# Sheet2.net
KiCad netlist of a schematic drawn in Altium Designer
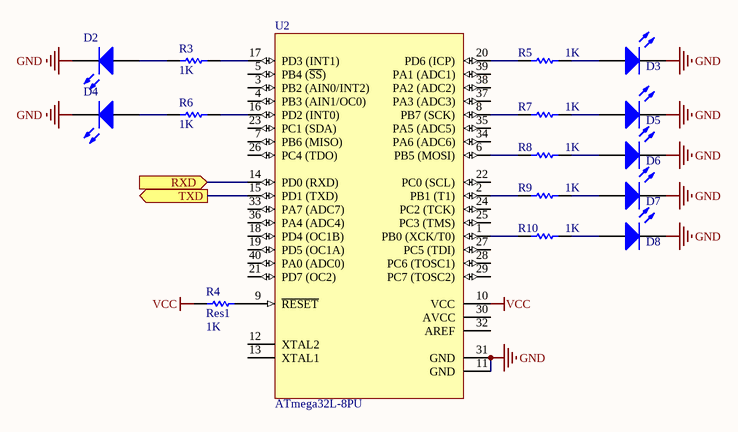
[diagram p0: Sheet2.SchDoc]

(export (version "E")
  (design (tool "Eeschema 10.0.6"))
  (components
    (comp (ref "D2")
      (value "LED0")
      (footprint "LED-0")
      (description "Typical INFRARED GaAs LED")
      (fields (field (name "PUBLISHER") "Altium Limited"))
      (libsource (lib "Miscellaneous Devices") (part "LED0"))
    )
    (comp (ref "D3")
      (value "LED0")
      (footprint "LED-0")
      (description "Typical INFRARED GaAs LED")
      (fields (field (name "PUBLISHER") "Altium Limited"))
      (libsource (lib "Miscellaneous Devices") (part "LED0"))
    )
    (comp (ref "D4")
      (value "LED0")
      (footprint "LED-0")
      (description "Typical INFRARED GaAs LED")
      (fields (field (name "PUBLISHER") "Altium Limited"))
      (libsource (lib "Miscellaneous Devices") (part "LED0"))
    )
    (comp (ref "D5")
      (value "LED0")
      (footprint "LED-0")
      (description "Typical INFRARED GaAs LED")
      (fields (field (name "PUBLISHER") "Altium Limited"))
      (libsource (lib "Miscellaneous Devices") (part "LED0"))
    )
    (comp (ref "D6")
      (value "LED0")
      (footprint "LED-0")
      (description "Typical INFRARED GaAs LED")
      (fields (field (name "PUBLISHER") "Altium Limited"))
      (libsource (lib "Miscellaneous Devices") (part "LED0"))
    )
    (comp (ref "D7")
      (value "LED0")
      (footprint "LED-0")
      (description "Typical INFRARED GaAs LED")
      (fields (field (name "PUBLISHER") "Altium Limited"))
      (libsource (lib "Miscellaneous Devices") (part "LED0"))
    )
    (comp (ref "D8")
      (value "LED0")
      (footprint "LED-0")
      (description "Typical INFRARED GaAs LED")
      (fields (field (name "PUBLISHER") "Altium Limited"))
      (libsource (lib "Miscellaneous Devices") (part "LED0"))
    )
    (comp (ref "R3")
      (value "1K")
      (footprint "AXIAL-0.3")
      (description "Resistor")
      (fields (field (name "Comment") "Res1") (field (name "PUBLISHER") "Altium Limited"))
      (libsource (lib "Miscellaneous Devices") (part "Res1"))
    )
    (comp (ref "R4")
      (value "Res1")
      (footprint "AXIAL-0.3")
      (description "Resistor")
      (fields (field (name "ALTIUM_VALUE") "1K") (field (name "PUBLISHER") "Altium Limited"))
      (libsource (lib "Miscellaneous Devices") (part "Res1"))
    )
    (comp (ref "R5")
      (value "1K")
      (footprint "AXIAL-0.3")
      (description "Resistor")
      (fields (field (name "Comment") "Res1") (field (name "PUBLISHER") "Altium Limited"))
      (libsource (lib "Miscellaneous Devices") (part "Res1"))
    )
    (comp (ref "R6")
      (value "1K")
      (footprint "AXIAL-0.3")
      (description "Resistor")
      (fields (field (name "Comment") "Res1") (field (name "PUBLISHER") "Altium Limited"))
      (libsource (lib "Miscellaneous Devices") (part "Res1"))
    )
    (comp (ref "R7")
      (value "1K")
      (footprint "AXIAL-0.3")
      (description "Resistor")
      (fields (field (name "Comment") "Res1") (field (name "PUBLISHER") "Altium Limited"))
      (libsource (lib "Miscellaneous Devices") (part "Res1"))
    )
    (comp (ref "R8")
      (value "1K")
      (footprint "AXIAL-0.3")
      (description "Resistor")
      (fields (field (name "Comment") "Res1") (field (name "PUBLISHER") "Altium Limited"))
      (libsource (lib "Miscellaneous Devices") (part "Res1"))
    )
    (comp (ref "R9")
      (value "1K")
      (footprint "AXIAL-0.3")
      (description "Resistor")
      (fields (field (name "Comment") "Res1") (field (name "PUBLISHER") "Altium Limited"))
      (libsource (lib "Miscellaneous Devices") (part "Res1"))
    )
    (comp (ref "R10")
      (value "1K")
      (footprint "AXIAL-0.3")
      (description "Resistor")
      (fields (field (name "Comment") "Res1") (field (name "PUBLISHER") "Altium Limited"))
      (libsource (lib "Miscellaneous Devices") (part "Res1"))
    )
    (comp (ref "U2")
      (value "ATmega32L-8PU")
      (footprint "40P6")
      (libsource (lib "Atmel Microcontroller megaAVR") (part "ATmega32L-8PU"))
    )
  )
  (nets
    (net (code "1") (name "/RXD") (class "Default")
      (node (ref "U2") (pin "14") (pinfunction "PD0_(RXD)_14") (pintype "bidirectional"))
    )
    (net (code "2") (name "/TXD") (class "Default")
      (node (ref "U2") (pin "15") (pinfunction "PD1_(TXD)_15") (pintype "bidirectional"))
    )
    (net (code "3") (name "GND") (class "Default")
      (node (ref "D2") (pin "2") (pinfunction "K_2") (pintype "passive"))
      (node (ref "D3") (pin "2") (pinfunction "K_2") (pintype "passive"))
      (node (ref "D4") (pin "2") (pinfunction "K_2") (pintype "passive"))
      (node (ref "D5") (pin "2") (pinfunction "K_2") (pintype "passive"))
      (node (ref "D6") (pin "2") (pinfunction "K_2") (pintype "passive"))
      (node (ref "D7") (pin "2") (pinfunction "K_2") (pintype "passive"))
      (node (ref "D8") (pin "2") (pinfunction "K_2") (pintype "passive"))
      (node (ref "U2") (pin "11") (pinfunction "GND_11") (pintype "power_in"))
      (node (ref "U2") (pin "31") (pinfunction "GND_31") (pintype "power_in"))
    )
    (net (code "4") (name "Net-(D2-A)") (class "Default")
      (node (ref "D2") (pin "1") (pinfunction "A_1") (pintype "passive"))
      (node (ref "R3") (pin "2") (pinfunction "2_2") (pintype "passive"))
    )
    (net (code "5") (name "Net-(D3-A)") (class "Default")
      (node (ref "D3") (pin "1") (pinfunction "A_1") (pintype "passive"))
      (node (ref "R5") (pin "2") (pinfunction "2_2") (pintype "passive"))
    )
    (net (code "6") (name "Net-(D4-A)") (class "Default")
      (node (ref "D4") (pin "1") (pinfunction "A_1") (pintype "passive"))
      (node (ref "R6") (pin "2") (pinfunction "2_2") (pintype "passive"))
    )
    (net (code "7") (name "Net-(D5-A)") (class "Default")
      (node (ref "D5") (pin "1") (pinfunction "A_1") (pintype "passive"))
      (node (ref "R7") (pin "2") (pinfunction "2_2") (pintype "passive"))
    )
    (net (code "8") (name "Net-(D6-A)") (class "Default")
      (node (ref "D6") (pin "1") (pinfunction "A_1") (pintype "passive"))
      (node (ref "R8") (pin "2") (pinfunction "2_2") (pintype "passive"))
    )
    (net (code "9") (name "Net-(D7-A)") (class "Default")
      (node (ref "D7") (pin "1") (pinfunction "A_1") (pintype "passive"))
      (node (ref "R9") (pin "2") (pinfunction "2_2") (pintype "passive"))
    )
    (net (code "10") (name "Net-(D8-A)") (class "Default")
      (node (ref "D8") (pin "1") (pinfunction "A_1") (pintype "passive"))
      (node (ref "R10") (pin "2") (pinfunction "2_2") (pintype "passive"))
    )
    (net (code "11") (name "Net-(U2-PB0_(XCK{slash}T0))") (class "Default")
      (node (ref "R10") (pin "1") (pinfunction "1_1") (pintype "passive"))
      (node (ref "U2") (pin "1") (pinfunction "PB0_(XCK/T0)_1") (pintype "bidirectional"))
    )
    (net (code "12") (name "Net-(U2-PB1_(T1))") (class "Default")
      (node (ref "R9") (pin "1") (pinfunction "1_1") (pintype "passive"))
      (node (ref "U2") (pin "2") (pinfunction "PB1_(T1)_2") (pintype "bidirectional"))
    )
    (net (code "13") (name "Net-(U2-PB5_(MOSI))") (class "Default")
      (node (ref "R8") (pin "1") (pinfunction "1_1") (pintype "passive"))
      (node (ref "U2") (pin "6") (pinfunction "PB5_(MOSI)_6") (pintype "bidirectional"))
    )
    (net (code "14") (name "Net-(U2-PB7_(SCK))") (class "Default")
      (node (ref "R7") (pin "1") (pinfunction "1_1") (pintype "passive"))
      (node (ref "U2") (pin "8") (pinfunction "PB7_(SCK)_8") (pintype "bidirectional"))
    )
    (net (code "15") (name "Net-(U2-PD2_(INT0))") (class "Default")
      (node (ref "R6") (pin "1") (pinfunction "1_1") (pintype "passive"))
      (node (ref "U2") (pin "16") (pinfunction "PD2_(INT0)_16") (pintype "bidirectional"))
    )
    (net (code "16") (name "Net-(U2-PD3_(INT1))") (class "Default")
      (node (ref "R3") (pin "1") (pinfunction "1_1") (pintype "passive"))
      (node (ref "U2") (pin "17") (pinfunction "PD3_(INT1)_17") (pintype "bidirectional"))
    )
    (net (code "17") (name "Net-(U2-PD6_(ICP))") (class "Default")
      (node (ref "R5") (pin "1") (pinfunction "1_1") (pintype "passive"))
      (node (ref "U2") (pin "20") (pinfunction "PD6_(ICP)_20") (pintype "bidirectional"))
    )
    (net (code "18") (name "Net-(U2-~{RESET})") (class "Default")
      (node (ref "R4") (pin "2") (pinfunction "2_2") (pintype "passive"))
      (node (ref "U2") (pin "9") (pinfunction "~{RESET}_9") (pintype "input"))
    )
    (net (code "19") (name "VCC") (class "Default")
      (node (ref "R4") (pin "1") (pinfunction "1_1") (pintype "passive"))
      (node (ref "U2") (pin "10") (pinfunction "VCC_10") (pintype "power_in"))
    )
    (net (code "20") (name "unconnected-(U2-AREF-Pad32)") (class "Default")
      (node (ref "U2") (pin "32") (pinfunction "AREF_32") (pintype "passive"))
    )
    (net (code "21") (name "unconnected-(U2-AVCC-Pad30)") (class "Default")
      (node (ref "U2") (pin "30") (pinfunction "AVCC_30") (pintype "power_in"))
    )
    (net (code "22") (name "unconnected-(U2-PA0_(ADC0)-Pad40)") (class "Default")
      (node (ref "U2") (pin "40") (pinfunction "PA0_(ADC0)_40") (pintype "bidirectional"))
    )
    (net (code "23") (name "unconnected-(U2-PA1_(ADC1)-Pad39)") (class "Default")
      (node (ref "U2") (pin "39") (pinfunction "PA1_(ADC1)_39") (pintype "bidirectional"))
    )
    (net (code "24") (name "unconnected-(U2-PA2_(ADC2)-Pad38)") (class "Default")
      (node (ref "U2") (pin "38") (pinfunction "PA2_(ADC2)_38") (pintype "bidirectional"))
    )
    (net (code "25") (name "unconnected-(U2-PA3_(ADC3)-Pad37)") (class "Default")
      (node (ref "U2") (pin "37") (pinfunction "PA3_(ADC3)_37") (pintype "bidirectional"))
    )
    (net (code "26") (name "unconnected-(U2-PA4_(ADC4)-Pad36)") (class "Default")
      (node (ref "U2") (pin "36") (pinfunction "PA4_(ADC4)_36") (pintype "bidirectional"))
    )
    (net (code "27") (name "unconnected-(U2-PA5_(ADC5)-Pad35)") (class "Default")
      (node (ref "U2") (pin "35") (pinfunction "PA5_(ADC5)_35") (pintype "bidirectional"))
    )
    (net (code "28") (name "unconnected-(U2-PA6_(ADC6)-Pad34)") (class "Default")
      (node (ref "U2") (pin "34") (pinfunction "PA6_(ADC6)_34") (pintype "bidirectional"))
    )
    (net (code "29") (name "unconnected-(U2-PA7_(ADC7)-Pad33)") (class "Default")
      (node (ref "U2") (pin "33") (pinfunction "PA7_(ADC7)_33") (pintype "bidirectional"))
    )
    (net (code "30") (name "unconnected-(U2-PB2_(AIN0{slash}INT2)-Pad3)") (class "Default")
      (node (ref "U2") (pin "3") (pinfunction "PB2_(AIN0/INT2)_3") (pintype "bidirectional"))
    )
    (net (code "31") (name "unconnected-(U2-PB3_(AIN1{slash}OC0)-Pad4)") (class "Default")
      (node (ref "U2") (pin "4") (pinfunction "PB3_(AIN1/OC0)_4") (pintype "bidirectional"))
    )
    (net (code "32") (name "unconnected-(U2-PB4_(~{SS})-Pad5)") (class "Default")
      (node (ref "U2") (pin "5") (pinfunction "PB4_(~{SS})_5") (pintype "bidirectional"))
    )
    (net (code "33") (name "unconnected-(U2-PB6_(MISO)-Pad7)") (class "Default")
      (node (ref "U2") (pin "7") (pinfunction "PB6_(MISO)_7") (pintype "bidirectional"))
    )
    (net (code "34") (name "unconnected-(U2-PC0_(SCL)-Pad22)") (class "Default")
      (node (ref "U2") (pin "22") (pinfunction "PC0_(SCL)_22") (pintype "bidirectional"))
    )
    (net (code "35") (name "unconnected-(U2-PC1_(SDA)-Pad23)") (class "Default")
      (node (ref "U2") (pin "23") (pinfunction "PC1_(SDA)_23") (pintype "bidirectional"))
    )
    (net (code "36") (name "unconnected-(U2-PC2_(TCK)-Pad24)") (class "Default")
      (node (ref "U2") (pin "24") (pinfunction "PC2_(TCK)_24") (pintype "bidirectional"))
    )
    (net (code "37") (name "unconnected-(U2-PC3_(TMS)-Pad25)") (class "Default")
      (node (ref "U2") (pin "25") (pinfunction "PC3_(TMS)_25") (pintype "bidirectional"))
    )
    (net (code "38") (name "unconnected-(U2-PC4_(TDO)-Pad26)") (class "Default")
      (node (ref "U2") (pin "26") (pinfunction "PC4_(TDO)_26") (pintype "bidirectional"))
    )
    (net (code "39") (name "unconnected-(U2-PC5_(TDI)-Pad27)") (class "Default")
      (node (ref "U2") (pin "27") (pinfunction "PC5_(TDI)_27") (pintype "bidirectional"))
    )
    (net (code "40") (name "unconnected-(U2-PC6_(TOSC1)-Pad28)") (class "Default")
      (node (ref "U2") (pin "28") (pinfunction "PC6_(TOSC1)_28") (pintype "bidirectional"))
    )
    (net (code "41") (name "unconnected-(U2-PC7_(TOSC2)-Pad29)") (class "Default")
      (node (ref "U2") (pin "29") (pinfunction "PC7_(TOSC2)_29") (pintype "bidirectional"))
    )
    (net (code "42") (name "unconnected-(U2-PD4_(OC1B)-Pad18)") (class "Default")
      (node (ref "U2") (pin "18") (pinfunction "PD4_(OC1B)_18") (pintype "bidirectional"))
    )
    (net (code "43") (name "unconnected-(U2-PD5_(OC1A)-Pad19)") (class "Default")
      (node (ref "U2") (pin "19") (pinfunction "PD5_(OC1A)_19") (pintype "bidirectional"))
    )
    (net (code "44") (name "unconnected-(U2-PD7_(OC2)-Pad21)") (class "Default")
      (node (ref "U2") (pin "21") (pinfunction "PD7_(OC2)_21") (pintype "bidirectional"))
    )
    (net (code "45") (name "unconnected-(U2-XTAL1-Pad13)") (class "Default")
      (node (ref "U2") (pin "13") (pinfunction "XTAL1_13") (pintype "passive"))
    )
    (net (code "46") (name "unconnected-(U2-XTAL2-Pad12)") (class "Default")
      (node (ref "U2") (pin "12") (pinfunction "XTAL2_12") (pintype "passive"))
    )
  )
)
